# Dice.net
KiCad netlist of a schematic drawn in EAGLE
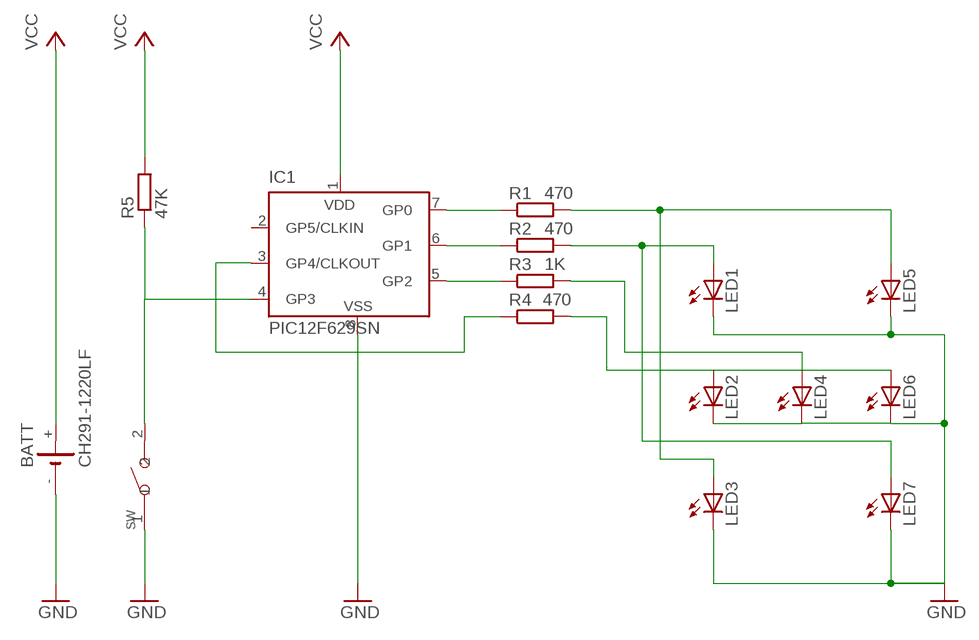
[diagram p0: schematic, sheet 1]

(export (version "E")
  (design (tool "Eeschema 10.0.6"))
  (components
    (comp (ref "BATT")
      (value "CH291-1220LF")
      (footprint "eagle-import:CH291-1220LF")
      (libsource (lib "eagle-import") (part "CH291-1220LF"))
    )
    (comp (ref "IC1")
      (value "PIC12F629SN")
      (footprint "eagle-import:SO-08")
      (fields (field (name "MF") "MICROCHIP") (field (name "MPN") "PIC12F629-I/SN"))
      (libsource (lib "eagle-import") (part "PIC12F6SN29"))
    )
    (comp (ref "LED1")
      (value "LEDCHIPLED_0805")
      (footprint "eagle-import:CHIPLED_0805")
      (libsource (lib "eagle-import") (part "LEDCHIPLED_0805"))
    )
    (comp (ref "LED2")
      (value "LEDCHIPLED_0805")
      (footprint "eagle-import:CHIPLED_0805")
      (libsource (lib "eagle-import") (part "LEDCHIPLED_0805"))
    )
    (comp (ref "LED3")
      (value "LEDCHIPLED_0805")
      (footprint "eagle-import:CHIPLED_0805")
      (libsource (lib "eagle-import") (part "LEDCHIPLED_0805"))
    )
    (comp (ref "LED4")
      (value "LEDCHIPLED_0805")
      (footprint "eagle-import:CHIPLED_0805")
      (libsource (lib "eagle-import") (part "LEDCHIPLED_0805"))
    )
    (comp (ref "LED5")
      (value "LEDCHIPLED_0805")
      (footprint "eagle-import:CHIPLED_0805")
      (libsource (lib "eagle-import") (part "LEDCHIPLED_0805"))
    )
    (comp (ref "LED6")
      (value "LEDCHIPLED_0805")
      (footprint "eagle-import:CHIPLED_0805")
      (libsource (lib "eagle-import") (part "LEDCHIPLED_0805"))
    )
    (comp (ref "LED7")
      (value "LEDCHIPLED_0805")
      (footprint "eagle-import:CHIPLED_0805")
      (libsource (lib "eagle-import") (part "LEDCHIPLED_0805"))
    )
    (comp (ref "R1")
      (value "470")
      (footprint "eagle-import:R0805")
      (libsource (lib "eagle-import") (part "R-EU_R0805"))
    )
    (comp (ref "R2")
      (value "470")
      (footprint "eagle-import:R0805")
      (libsource (lib "eagle-import") (part "R-EU_R0805"))
    )
    (comp (ref "R3")
      (value "1K")
      (footprint "eagle-import:R0805")
      (libsource (lib "eagle-import") (part "R-EU_R0805"))
    )
    (comp (ref "R4")
      (value "470")
      (footprint "eagle-import:R0805")
      (libsource (lib "eagle-import") (part "R-EU_R0805"))
    )
    (comp (ref "R5")
      (value "47K")
      (footprint "eagle-import:R0805")
      (libsource (lib "eagle-import") (part "R-EU_R0805"))
    )
    (comp (ref "SW")
      (value "SMD-BUTTON(2P-6.0X3.0X2.5MM)-DHT-1163S")
      (footprint "eagle-import:SW2-4.0-6.0X3.0X2.5MM")
      (libsource (lib "eagle-import") (part "SMD-BUTTON(2P-6.0X3.0X2.5MM)-DHT-1163S"))
    )
  )
  (nets
    (net (code "1") (name "GND") (class "Default")
      (node (ref "BATT") (pin "-") (pinfunction "-_-") (pintype "passive"))
      (node (ref "IC1") (pin "8") (pinfunction "VSS_8") (pintype "power_in"))
      (node (ref "LED1") (pin "C") (pinfunction "C_C") (pintype "passive"))
      (node (ref "LED2") (pin "C") (pinfunction "C_C") (pintype "passive"))
      (node (ref "LED3") (pin "C") (pinfunction "C_C") (pintype "passive"))
      (node (ref "LED4") (pin "C") (pinfunction "C_C") (pintype "passive"))
      (node (ref "LED5") (pin "C") (pinfunction "C_C") (pintype "passive"))
      (node (ref "LED6") (pin "C") (pinfunction "C_C") (pintype "passive"))
      (node (ref "LED7") (pin "C") (pinfunction "C_C") (pintype "passive"))
      (node (ref "SW") (pin "1") (pinfunction "1_1") (pintype "bidirectional"))
    )
    (net (code "2") (name "Net-(IC1-GP0)") (class "Default")
      (node (ref "IC1") (pin "7") (pinfunction "GP0_7") (pintype "bidirectional"))
      (node (ref "R1") (pin "1") (pinfunction "1_1") (pintype "passive"))
    )
    (net (code "3") (name "Net-(IC1-GP1)") (class "Default")
      (node (ref "IC1") (pin "6") (pinfunction "GP1_6") (pintype "bidirectional"))
      (node (ref "R2") (pin "1") (pinfunction "1_1") (pintype "passive"))
    )
    (net (code "4") (name "Net-(IC1-GP2)") (class "Default")
      (node (ref "IC1") (pin "5") (pinfunction "GP2_5") (pintype "bidirectional"))
      (node (ref "R3") (pin "1") (pinfunction "1_1") (pintype "passive"))
    )
    (net (code "5") (name "Net-(IC1-GP3)") (class "Default")
      (node (ref "IC1") (pin "4") (pinfunction "GP3_4") (pintype "input"))
      (node (ref "R5") (pin "1") (pinfunction "1_1") (pintype "passive"))
      (node (ref "SW") (pin "2") (pinfunction "2_2") (pintype "bidirectional"))
    )
    (net (code "6") (name "Net-(IC1-GP4{slash}CLKOUT)") (class "Default")
      (node (ref "IC1") (pin "3") (pinfunction "GP4/CLKOUT_3") (pintype "bidirectional"))
      (node (ref "R4") (pin "1") (pinfunction "1_1") (pintype "passive"))
    )
    (net (code "7") (name "Net-(LED1-PadA)") (class "Default")
      (node (ref "LED1") (pin "A") (pinfunction "A_A") (pintype "passive"))
      (node (ref "LED7") (pin "A") (pinfunction "A_A") (pintype "passive"))
      (node (ref "R2") (pin "2") (pinfunction "2_2") (pintype "passive"))
    )
    (net (code "8") (name "Net-(LED2-PadA)") (class "Default")
      (node (ref "LED2") (pin "A") (pinfunction "A_A") (pintype "passive"))
      (node (ref "LED6") (pin "A") (pinfunction "A_A") (pintype "passive"))
      (node (ref "R4") (pin "2") (pinfunction "2_2") (pintype "passive"))
    )
    (net (code "9") (name "Net-(LED3-PadA)") (class "Default")
      (node (ref "LED3") (pin "A") (pinfunction "A_A") (pintype "passive"))
      (node (ref "LED5") (pin "A") (pinfunction "A_A") (pintype "passive"))
      (node (ref "R1") (pin "2") (pinfunction "2_2") (pintype "passive"))
    )
    (net (code "10") (name "Net-(LED4-PadA)") (class "Default")
      (node (ref "LED4") (pin "A") (pinfunction "A_A") (pintype "passive"))
      (node (ref "R3") (pin "2") (pinfunction "2_2") (pintype "passive"))
    )
    (net (code "11") (name "VCC") (class "Default")
      (node (ref "BATT") (pin "+") (pinfunction "+_+") (pintype "passive"))
      (node (ref "IC1") (pin "1") (pinfunction "VDD_1") (pintype "power_in"))
      (node (ref "R5") (pin "2") (pinfunction "2_2") (pintype "passive"))
    )
    (net (code "12") (name "unconnected-(IC1-GP5{slash}CLKIN-Pad2)") (class "Default")
      (node (ref "IC1") (pin "2") (pinfunction "GP5/CLKIN_2") (pintype "bidirectional"))
    )
  )
)
